# Controller.net
KiCad netlist of a schematic drawn in Altium Designer
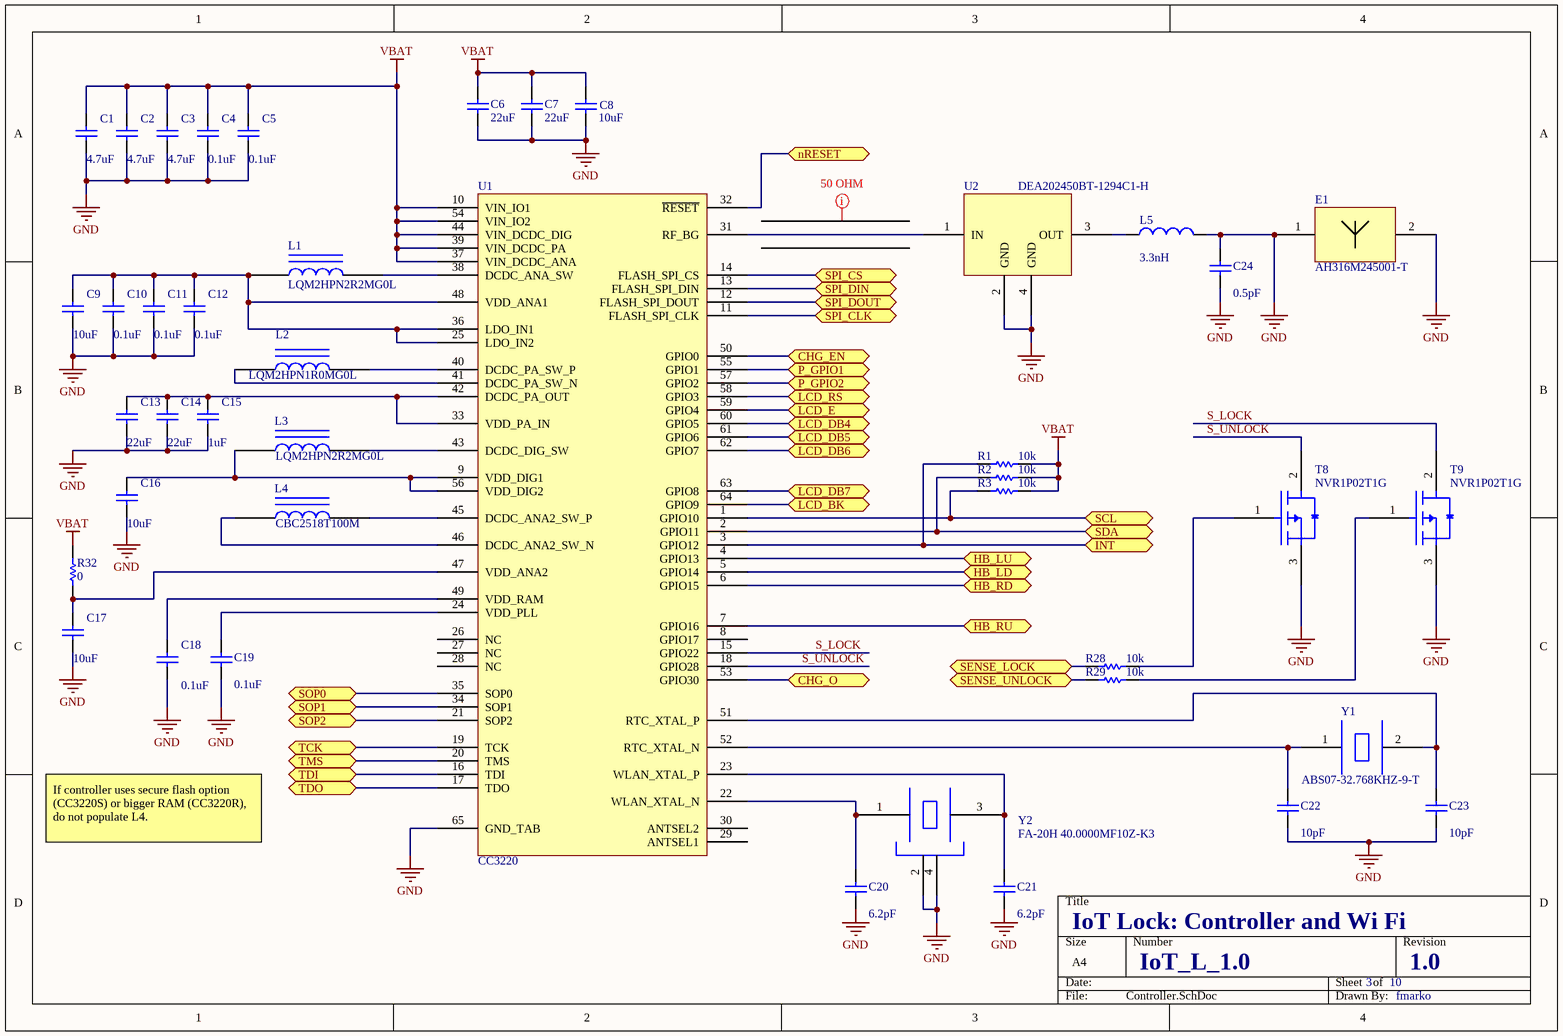
[diagram p0: Controller.SchDoc]

(export (version "E")
  (design (tool "Eeschema 10.0.6"))
  (components
    (comp (ref "C1")
      (value "4.7uF")
      (footprint "0402")
      (description "Capacitor")
      (fields (field (name "Comment") "GRM1555C1HR50BA01D") (field (name "PUBLISHER") "Altium Limited"))
      (libsource (lib "Miscellaneous Devices") (part "Cap"))
    )
    (comp (ref "C2")
      (value "4.7uF")
      (footprint "0402")
      (description "Capacitor")
      (fields (field (name "Comment") "GRM1555C1HR50BA01D") (field (name "PUBLISHER") "Altium Limited"))
      (libsource (lib "Miscellaneous Devices") (part "Cap"))
    )
    (comp (ref "C3")
      (value "4.7uF")
      (footprint "0402")
      (description "Capacitor")
      (fields (field (name "Comment") "GRM1555C1HR50BA01D") (field (name "PUBLISHER") "Altium Limited"))
      (libsource (lib "Miscellaneous Devices") (part "Cap"))
    )
    (comp (ref "C4")
      (value "0.1uF")
      (footprint "0402")
      (description "Capacitor")
      (fields (field (name "Comment") "GRM1555C1HR50BA01D") (field (name "PUBLISHER") "Altium Limited"))
      (libsource (lib "Miscellaneous Devices") (part "Cap"))
    )
    (comp (ref "C5")
      (value "0.1uF")
      (footprint "0402")
      (description "Capacitor")
      (fields (field (name "Comment") "GRM1555C1HR50BA01D") (field (name "PUBLISHER") "Altium Limited"))
      (libsource (lib "Miscellaneous Devices") (part "Cap"))
    )
    (comp (ref "C6")
      (value "22uF")
      (footprint "1608[0603]")
      (description "Capacitor")
      (fields (field (name "Comment") "GRM1555C1HR50BA01D") (field (name "PUBLISHER") "Altium Limited"))
      (libsource (lib "Miscellaneous Devices") (part "Cap"))
    )
    (comp (ref "C7")
      (value "22uF")
      (footprint "1608[0603]")
      (description "Capacitor")
      (fields (field (name "Comment") "GRM1555C1HR50BA01D") (field (name "PUBLISHER") "Altium Limited"))
      (libsource (lib "Miscellaneous Devices") (part "Cap"))
    )
    (comp (ref "C8")
      (value "10uF")
      (footprint "1608[0603]")
      (description "Capacitor")
      (fields (field (name "Comment") "GRM1555C1HR50BA01D") (field (name "PUBLISHER") "Altium Limited"))
      (libsource (lib "Miscellaneous Devices") (part "Cap"))
    )
    (comp (ref "C9")
      (value "10uF")
      (footprint "1608[0603]")
      (description "Capacitor")
      (fields (field (name "Comment") "GRM1555C1HR50BA01D") (field (name "PUBLISHER") "Altium Limited"))
      (libsource (lib "Miscellaneous Devices") (part "Cap"))
    )
    (comp (ref "C10")
      (value "0.1uF")
      (footprint "0402")
      (description "Capacitor")
      (fields (field (name "Comment") "GRM1555C1HR50BA01D") (field (name "PUBLISHER") "Altium Limited"))
      (libsource (lib "Miscellaneous Devices") (part "Cap"))
    )
    (comp (ref "C11")
      (value "0.1uF")
      (footprint "0402")
      (description "Capacitor")
      (fields (field (name "Comment") "GRM1555C1HR50BA01D") (field (name "PUBLISHER") "Altium Limited"))
      (libsource (lib "Miscellaneous Devices") (part "Cap"))
    )
    (comp (ref "C12")
      (value "0.1uF")
      (footprint "0402")
      (description "Capacitor")
      (fields (field (name "Comment") "GRM1555C1HR50BA01D") (field (name "PUBLISHER") "Altium Limited"))
      (libsource (lib "Miscellaneous Devices") (part "Cap"))
    )
    (comp (ref "C13")
      (value "22uF")
      (footprint "1608[0603]")
      (description "Capacitor")
      (fields (field (name "Comment") "GRM1555C1HR50BA01D") (field (name "PUBLISHER") "Altium Limited"))
      (libsource (lib "Miscellaneous Devices") (part "Cap"))
    )
    (comp (ref "C14")
      (value "22uF")
      (footprint "1608[0603]")
      (description "Capacitor")
      (fields (field (name "Comment") "GRM1555C1HR50BA01D") (field (name "PUBLISHER") "Altium Limited"))
      (libsource (lib "Miscellaneous Devices") (part "Cap"))
    )
    (comp (ref "C15")
      (value "1uF")
      (footprint "0402")
      (description "Capacitor")
      (fields (field (name "Comment") "GRM1555C1HR50BA01D") (field (name "PUBLISHER") "Altium Limited"))
      (libsource (lib "Miscellaneous Devices") (part "Cap"))
    )
    (comp (ref "C16")
      (value "10uF")
      (footprint "1608[0603]")
      (description "Capacitor")
      (fields (field (name "Comment") "GRM1555C1HR50BA01D") (field (name "PUBLISHER") "Altium Limited"))
      (libsource (lib "Miscellaneous Devices") (part "Cap"))
    )
    (comp (ref "C17")
      (value "10uF")
      (footprint "1608[0603]")
      (description "Capacitor")
      (fields (field (name "Comment") "GRM1555C1HR50BA01D") (field (name "PUBLISHER") "Altium Limited"))
      (libsource (lib "Miscellaneous Devices") (part "Cap"))
    )
    (comp (ref "C18")
      (value "0.1uF")
      (footprint "0402")
      (description "Capacitor")
      (fields (field (name "Comment") "GRM1555C1HR50BA01D") (field (name "PUBLISHER") "Altium Limited"))
      (libsource (lib "Miscellaneous Devices") (part "Cap"))
    )
    (comp (ref "C19")
      (value "0.1uF")
      (footprint "0402")
      (description "Capacitor")
      (fields (field (name "Comment") "GRM1555C1HR50BA01D") (field (name "PUBLISHER") "Altium Limited"))
      (libsource (lib "Miscellaneous Devices") (part "Cap"))
    )
    (comp (ref "C20")
      (value "6.2pF")
      (footprint "0402")
      (description "Capacitor")
      (fields (field (name "Comment") "GRM1555C1HR50BA01D") (field (name "PUBLISHER") "Altium Limited"))
      (libsource (lib "Miscellaneous Devices") (part "Cap"))
    )
    (comp (ref "C21")
      (value "6.2pF")
      (footprint "0402")
      (description "Capacitor")
      (fields (field (name "Comment") "GRM1555C1HR50BA01D") (field (name "PUBLISHER") "Altium Limited"))
      (libsource (lib "Miscellaneous Devices") (part "Cap"))
    )
    (comp (ref "C22")
      (value "10pF")
      (footprint "0402")
      (description "Capacitor")
      (fields (field (name "Comment") "GRM1555C1HR50BA01D") (field (name "PUBLISHER") "Altium Limited"))
      (libsource (lib "Miscellaneous Devices") (part "Cap"))
    )
    (comp (ref "C23")
      (value "10pF")
      (footprint "0402")
      (description "Capacitor")
      (fields (field (name "Comment") "GRM1555C1HR50BA01D") (field (name "PUBLISHER") "Altium Limited"))
      (libsource (lib "Miscellaneous Devices") (part "Cap"))
    )
    (comp (ref "C24")
      (value "0.5pF")
      (footprint "0402")
      (description "Capacitor")
      (fields (field (name "Comment") "GRM1555C1HR50BA01D") (field (name "PUBLISHER") "Altium Limited"))
      (libsource (lib "Miscellaneous Devices") (part "Cap"))
    )
    (comp (ref "E1")
      (value "AH316M245001-T")
      (footprint "AH316M245001-T")
      (description "2.4 GHz Antenna")
      (libsource (lib "AH316M245001-T") (part "AH316M245001-T"))
    )
    (comp (ref "L1")
      (value "LQM2HPN2R2MG0L")
      (footprint "INDC2520X10N")
      (description "Murata 2.2uH inductor")
      (libsource (lib "LQM2HPN2R2MG0L") (part "LQM2HPN2R2MG0L"))
    )
    (comp (ref "L2")
      (value "LQM2HPN1R0MG0L")
      (footprint "INDC2520X10N")
      (description "Murata 2.2uH inductor")
      (libsource (lib "LQM2HPN2R2MG0L") (part "LQM2HPN2R2MG0L"))
    )
    (comp (ref "L3")
      (value "LQM2HPN2R2MG0L")
      (footprint "INDC2520X10N")
      (description "Murata 2.2uH inductor")
      (libsource (lib "LQM2HPN2R2MG0L") (part "LQM2HPN2R2MG0L"))
    )
    (comp (ref "L4")
      (value "CBC2518T100M")
      (footprint "INDC2518X20N")
      (description "10 uH inductor, Taiyo Yuden")
      (libsource (lib "CBC2518T100M") (part "CBC2518T100M"))
    )
    (comp (ref "L5")
      (value "3.3nH")
      (footprint "0402-A")
      (description "Inductor")
      (fields (field (name "Comment") "LQG15HS3N3S02D") (field (name "PUBLISHER") "Altium Limited"))
      (libsource (lib "Miscellaneous Devices") (part "Inductor"))
    )
    (comp (ref "R1")
      (value "10k")
      (footprint "0402")
      (description "Semiconductor Resistor")
      (fields (field (name "Comment") "Res Semi") (field (name "PUBLISHER") "Altium Limited"))
      (libsource (lib "Miscellaneous Devices") (part "Res Semi"))
    )
    (comp (ref "R2")
      (value "10k")
      (footprint "0402")
      (description "Semiconductor Resistor")
      (fields (field (name "Comment") "Res Semi") (field (name "PUBLISHER") "Altium Limited"))
      (libsource (lib "Miscellaneous Devices") (part "Res Semi"))
    )
    (comp (ref "R3")
      (value "10k")
      (footprint "0402")
      (description "Semiconductor Resistor")
      (fields (field (name "Comment") "Res Semi") (field (name "PUBLISHER") "Altium Limited"))
      (libsource (lib "Miscellaneous Devices") (part "Res Semi"))
    )
    (comp (ref "R28")
      (value "10k")
      (footprint "0402")
      (description "Semiconductor Resistor")
      (fields (field (name "Comment") "Res Semi") (field (name "PUBLISHER") "Altium Limited"))
      (libsource (lib "Miscellaneous Devices") (part "Res Semi"))
    )
    (comp (ref "R29")
      (value "10k")
      (footprint "0402")
      (description "Semiconductor Resistor")
      (fields (field (name "Comment") "Res Semi") (field (name "PUBLISHER") "Altium Limited"))
      (libsource (lib "Miscellaneous Devices") (part "Res Semi"))
    )
    (comp (ref "R32")
      (value "0")
      (footprint "0402")
      (description "Semiconductor Resistor")
      (fields (field (name "Comment") "Res Semi") (field (name "PUBLISHER") "Altium Limited"))
      (libsource (lib "Miscellaneous Devices") (part "Res Semi"))
    )
    (comp (ref "T8")
      (value "NVR1P02T1G")
      (footprint "SOT95P237X111-3N")
      (description "P-Channel MOSFET")
      (libsource (lib "NVR1P02T1G") (part "NVR1P02T1G"))
    )
    (comp (ref "T9")
      (value "NVR1P02T1G")
      (footprint "SOT95P237X111-3N")
      (description "P-Channel MOSFET")
      (libsource (lib "NVR1P02T1G") (part "NVR1P02T1G"))
    )
    (comp (ref "U1")
      (value "CC3220")
      (footprint "PQFN50P900X900X100_HS-65N")
      (description "WiFi IoT controller, TI")
      (libsource (lib "CC3220") (part "CC3220"))
    )
    (comp (ref "U2")
      (value "DEA202450BT-1294C1-H")
      (footprint "DEA202450BT-1294C1-H_LAYOUT")
      (libsource (lib "DEA202450BT-1294C1-H") (part "DEA202450BT-1294C1-H"))
    )
    (comp (ref "Y1")
      (value "ABS07-32.768KHZ-9-T")
      (footprint "ABS07-32.768KHZ-9-T_HS")
      (description "32.768 kHz Crystal, Abracon LLC")
      (libsource (lib "ABS07-32.768KHZ-9-T") (part "ABS07-32.768KHZ-9-T"))
    )
    (comp (ref "Y2")
      (value "FA-20H 40.0000MF10Z-K3")
      (footprint "FA-20H 40.0000MF10Z-K3_HS")
      (description "Crystal, 40 MHz, 10pF, Epson")
      (libsource (lib "FA-20H 40.0000MF10Z-K3") (part "FA-20H 40.0000MF10Z-K3"))
    )
  )
  (nets
    (net (code "1") (name "/CHG_EN") (class "Default")
      (node (ref "U1") (pin "50") (pinfunction "GPIO0_50") (pintype "passive"))
    )
    (net (code "2") (name "/CHG_O") (class "Default")
      (node (ref "U1") (pin "53") (pinfunction "GPIO30_53") (pintype "passive"))
    )
    (net (code "3") (name "/HB_LD") (class "Default")
      (node (ref "U1") (pin "5") (pinfunction "GPIO14_5") (pintype "passive"))
    )
    (net (code "4") (name "/HB_LU") (class "Default")
      (node (ref "U1") (pin "4") (pinfunction "GPIO13_4") (pintype "passive"))
    )
    (net (code "5") (name "/HB_RD") (class "Default")
      (node (ref "U1") (pin "6") (pinfunction "GPIO15_6") (pintype "passive"))
    )
    (net (code "6") (name "/HB_RU") (class "Default")
      (node (ref "U1") (pin "7") (pinfunction "GPIO16_7") (pintype "passive"))
    )
    (net (code "7") (name "/INT") (class "Default")
      (node (ref "R1") (pin "1") (pinfunction "1_1") (pintype "passive"))
      (node (ref "U1") (pin "3") (pinfunction "GPIO12_3") (pintype "passive"))
    )
    (net (code "8") (name "/LCD_BK") (class "Default")
      (node (ref "U1") (pin "64") (pinfunction "GPIO9_64") (pintype "passive"))
    )
    (net (code "9") (name "/LCD_DB4") (class "Default")
      (node (ref "U1") (pin "60") (pinfunction "GPIO5_60") (pintype "passive"))
    )
    (net (code "10") (name "/LCD_DB5") (class "Default")
      (node (ref "U1") (pin "61") (pinfunction "GPIO6_61") (pintype "passive"))
    )
    (net (code "11") (name "/LCD_DB6") (class "Default")
      (node (ref "U1") (pin "62") (pinfunction "GPIO7_62") (pintype "passive"))
    )
    (net (code "12") (name "/LCD_DB7") (class "Default")
      (node (ref "U1") (pin "63") (pinfunction "GPIO8_63") (pintype "passive"))
    )
    (net (code "13") (name "/LCD_E") (class "Default")
      (node (ref "U1") (pin "59") (pinfunction "GPIO4_59") (pintype "passive"))
    )
    (net (code "14") (name "/LCD_RS") (class "Default")
      (node (ref "U1") (pin "58") (pinfunction "GPIO3_58") (pintype "passive"))
    )
    (net (code "15") (name "/P_GPIO1") (class "Default")
      (node (ref "U1") (pin "55") (pinfunction "GPIO1_55") (pintype "passive"))
    )
    (net (code "16") (name "/P_GPIO2") (class "Default")
      (node (ref "U1") (pin "57") (pinfunction "GPIO2_57") (pintype "passive"))
    )
    (net (code "17") (name "/SCL") (class "Default")
      (node (ref "R3") (pin "1") (pinfunction "1_1") (pintype "passive"))
      (node (ref "U1") (pin "1") (pinfunction "GPIO10_1") (pintype "passive"))
    )
    (net (code "18") (name "/SDA") (class "Default")
      (node (ref "R2") (pin "1") (pinfunction "1_1") (pintype "passive"))
      (node (ref "U1") (pin "2") (pinfunction "GPIO11_2") (pintype "passive"))
    )
    (net (code "19") (name "/SENSE_LOCK") (class "Default")
      (node (ref "R28") (pin "1") (pinfunction "1_1") (pintype "passive"))
    )
    (net (code "20") (name "/SENSE_UNLOCK") (class "Default")
      (node (ref "R29") (pin "1") (pinfunction "1_1") (pintype "passive"))
    )
    (net (code "21") (name "/SOP0") (class "Default")
      (node (ref "U1") (pin "35") (pinfunction "SOP0_35") (pintype "passive"))
    )
    (net (code "22") (name "/SOP1") (class "Default")
      (node (ref "U1") (pin "34") (pinfunction "SOP1_34") (pintype "passive"))
    )
    (net (code "23") (name "/SOP2") (class "Default")
      (node (ref "U1") (pin "21") (pinfunction "SOP2_21") (pintype "passive"))
    )
    (net (code "24") (name "/SPI_CLK") (class "Default")
      (node (ref "U1") (pin "11") (pinfunction "FLASH_SPI_CLK_11") (pintype "passive"))
    )
    (net (code "25") (name "/SPI_CS") (class "Default")
      (node (ref "U1") (pin "14") (pinfunction "FLASH_SPI_CS_14") (pintype "passive"))
    )
    (net (code "26") (name "/SPI_DIN") (class "Default")
      (node (ref "U1") (pin "13") (pinfunction "FLASH_SPI_DIN_13") (pintype "passive"))
    )
    (net (code "27") (name "/SPI_DOUT") (class "Default")
      (node (ref "U1") (pin "12") (pinfunction "FLASH_SPI_DOUT_12") (pintype "passive"))
    )
    (net (code "28") (name "/S_LOCK") (class "Default")
      (node (ref "T9") (pin "2") (pinfunction "S_2") (pintype "passive"))
      (node (ref "U1") (pin "15") (pinfunction "GPIO22_15") (pintype "passive"))
    )
    (net (code "29") (name "/S_UNLOCK") (class "Default")
      (node (ref "T8") (pin "2") (pinfunction "S_2") (pintype "passive"))
      (node (ref "U1") (pin "18") (pinfunction "GPIO28_18") (pintype "passive"))
    )
    (net (code "30") (name "/TCK") (class "Default")
      (node (ref "U1") (pin "19") (pinfunction "TCK_19") (pintype "passive"))
    )
    (net (code "31") (name "/TDI") (class "Default")
      (node (ref "U1") (pin "16") (pinfunction "TDI_16") (pintype "passive"))
    )
    (net (code "32") (name "/TDO") (class "Default")
      (node (ref "U1") (pin "17") (pinfunction "TDO_17") (pintype "passive"))
    )
    (net (code "33") (name "/TMS") (class "Default")
      (node (ref "U1") (pin "20") (pinfunction "TMS_20") (pintype "passive"))
    )
    (net (code "34") (name "/nRESET") (class "Default")
      (node (ref "U1") (pin "32") (pinfunction "~{RESET}_32") (pintype "passive"))
    )
    (net (code "35") (name "GND") (class "Default")
      (node (ref "C1") (pin "1") (pinfunction "1_1") (pintype "passive"))
      (node (ref "C10") (pin "1") (pinfunction "1_1") (pintype "passive"))
      (node (ref "C11") (pin "1") (pinfunction "1_1") (pintype "passive"))
      (node (ref "C12") (pin "1") (pinfunction "1_1") (pintype "passive"))
      (node (ref "C13") (pin "1") (pinfunction "1_1") (pintype "passive"))
      (node (ref "C14") (pin "1") (pinfunction "1_1") (pintype "passive"))
      (node (ref "C15") (pin "1") (pinfunction "1_1") (pintype "passive"))
      (node (ref "C16") (pin "1") (pinfunction "1_1") (pintype "passive"))
      (node (ref "C17") (pin "1") (pinfunction "1_1") (pintype "passive"))
      (node (ref "C18") (pin "1") (pinfunction "1_1") (pintype "passive"))
      (node (ref "C19") (pin "1") (pinfunction "1_1") (pintype "passive"))
      (node (ref "C2") (pin "1") (pinfunction "1_1") (pintype "passive"))
      (node (ref "C20") (pin "1") (pinfunction "1_1") (pintype "passive"))
      (node (ref "C21") (pin "1") (pinfunction "1_1") (pintype "passive"))
      (node (ref "C22") (pin "1") (pinfunction "1_1") (pintype "passive"))
      (node (ref "C23") (pin "1") (pinfunction "1_1") (pintype "passive"))
      (node (ref "C24") (pin "1") (pinfunction "1_1") (pintype "passive"))
      (node (ref "C24") (pin "2") (pinfunction "2_2") (pintype "passive"))
      (node (ref "C3") (pin "1") (pinfunction "1_1") (pintype "passive"))
      (node (ref "C4") (pin "1") (pinfunction "1_1") (pintype "passive"))
      (node (ref "C5") (pin "1") (pinfunction "1_1") (pintype "passive"))
      (node (ref "C6") (pin "1") (pinfunction "1_1") (pintype "passive"))
      (node (ref "C7") (pin "1") (pinfunction "1_1") (pintype "passive"))
      (node (ref "C8") (pin "1") (pinfunction "1_1") (pintype "passive"))
      (node (ref "C9") (pin "1") (pinfunction "1_1") (pintype "passive"))
      (node (ref "E1") (pin "1") (pintype "passive"))
      (node (ref "E1") (pin "2") (pintype "passive"))
      (node (ref "L5") (pin "2") (pinfunction "2_2") (pintype "passive"))
      (node (ref "T8") (pin "3") (pinfunction "D_3") (pintype "passive"))
      (node (ref "T9") (pin "3") (pinfunction "D_3") (pintype "passive"))
      (node (ref "U1") (pin "65") (pinfunction "GND_TAB_65") (pintype "passive"))
      (node (ref "U2") (pin "2") (pinfunction "GND_2") (pintype "passive"))
      (node (ref "U2") (pin "4") (pinfunction "GND_4") (pintype "passive"))
      (node (ref "Y2") (pin "2") (pintype "passive"))
      (node (ref "Y2") (pin "4") (pintype "passive"))
    )
    (net (code "36") (name "Net-(T8-G)") (class "Default")
      (node (ref "R28") (pin "2") (pinfunction "2_2") (pintype "passive"))
      (node (ref "T8") (pin "1") (pinfunction "G_1") (pintype "passive"))
    )
    (net (code "37") (name "Net-(T9-G)") (class "Default")
      (node (ref "R29") (pin "2") (pinfunction "2_2") (pintype "passive"))
      (node (ref "T9") (pin "1") (pinfunction "G_1") (pintype "passive"))
    )
    (net (code "38") (name "Net-(U1-DCDC_ANA2_SW_N)") (class "Default")
      (node (ref "L4") (pin "1") (pinfunction "1_1") (pintype "passive"))
      (node (ref "U1") (pin "46") (pinfunction "DCDC_ANA2_SW_N_46") (pintype "passive"))
    )
    (net (code "39") (name "Net-(U1-DCDC_ANA2_SW_P)") (class "Default")
      (node (ref "L4") (pin "2") (pinfunction "2_2") (pintype "passive"))
      (node (ref "U1") (pin "45") (pinfunction "DCDC_ANA2_SW_P_45") (pintype "passive"))
    )
    (net (code "40") (name "Net-(U1-DCDC_ANA_SW)") (class "Default")
      (node (ref "L1") (pin "2") (pinfunction "2_2") (pintype "passive"))
      (node (ref "U1") (pin "38") (pinfunction "DCDC_ANA_SW_38") (pintype "passive"))
    )
    (net (code "41") (name "Net-(U1-DCDC_DIG_SW)") (class "Default")
      (node (ref "L3") (pin "2") (pinfunction "2_2") (pintype "passive"))
      (node (ref "U1") (pin "43") (pinfunction "DCDC_DIG_SW_43") (pintype "passive"))
    )
    (net (code "42") (name "Net-(U1-DCDC_PA_OUT)") (class "Default")
      (node (ref "C13") (pin "2") (pinfunction "2_2") (pintype "passive"))
      (node (ref "C14") (pin "2") (pinfunction "2_2") (pintype "passive"))
      (node (ref "C15") (pin "2") (pinfunction "2_2") (pintype "passive"))
      (node (ref "U1") (pin "33") (pinfunction "VDD_PA_IN_33") (pintype "passive"))
      (node (ref "U1") (pin "42") (pinfunction "DCDC_PA_OUT_42") (pintype "passive"))
    )
    (net (code "43") (name "Net-(U1-DCDC_PA_SW_N)") (class "Default")
      (node (ref "L2") (pin "1") (pinfunction "1_1") (pintype "passive"))
      (node (ref "U1") (pin "41") (pinfunction "DCDC_PA_SW_N_41") (pintype "passive"))
    )
    (net (code "44") (name "Net-(U1-DCDC_PA_SW_P)") (class "Default")
      (node (ref "L2") (pin "2") (pinfunction "2_2") (pintype "passive"))
      (node (ref "U1") (pin "40") (pinfunction "DCDC_PA_SW_P_40") (pintype "passive"))
    )
    (net (code "45") (name "Net-(U1-LDO_IN1)") (class "Default")
      (node (ref "C10") (pin "2") (pinfunction "2_2") (pintype "passive"))
      (node (ref "C11") (pin "2") (pinfunction "2_2") (pintype "passive"))
      (node (ref "C12") (pin "2") (pinfunction "2_2") (pintype "passive"))
      (node (ref "C9") (pin "2") (pinfunction "2_2") (pintype "passive"))
      (node (ref "L1") (pin "1") (pinfunction "1_1") (pintype "passive"))
      (node (ref "U1") (pin "25") (pinfunction "LDO_IN2_25") (pintype "passive"))
      (node (ref "U1") (pin "36") (pinfunction "LDO_IN1_36") (pintype "passive"))
      (node (ref "U1") (pin "48") (pinfunction "VDD_ANA1_48") (pintype "passive"))
    )
    (net (code "46") (name "Net-(U1-RF_BG)") (class "Default")
      (node (ref "U1") (pin "31") (pinfunction "RF_BG_31") (pintype "passive"))
      (node (ref "U2") (pin "1") (pinfunction "IN_1") (pintype "passive"))
    )
    (net (code "47") (name "Net-(U1-RTC_XTAL_N)") (class "Default")
      (node (ref "C22") (pin "2") (pinfunction "2_2") (pintype "passive"))
      (node (ref "U1") (pin "52") (pinfunction "RTC_XTAL_N_52") (pintype "passive"))
      (node (ref "Y1") (pin "1") (pintype "passive"))
    )
    (net (code "48") (name "Net-(U1-RTC_XTAL_P)") (class "Default")
      (node (ref "C23") (pin "2") (pinfunction "2_2") (pintype "passive"))
      (node (ref "U1") (pin "51") (pinfunction "RTC_XTAL_P_51") (pintype "passive"))
      (node (ref "Y1") (pin "2") (pintype "passive"))
    )
    (net (code "49") (name "Net-(U1-VDD_ANA2)") (class "Default")
      (node (ref "C17") (pin "2") (pinfunction "2_2") (pintype "passive"))
      (node (ref "R32") (pin "1") (pinfunction "1_1") (pintype "passive"))
      (node (ref "U1") (pin "47") (pinfunction "VDD_ANA2_47") (pintype "passive"))
    )
    (net (code "50") (name "Net-(U1-VDD_DIG1)") (class "Default")
      (node (ref "C16") (pin "2") (pinfunction "2_2") (pintype "passive"))
      (node (ref "L3") (pin "1") (pinfunction "1_1") (pintype "passive"))
      (node (ref "U1") (pin "56") (pinfunction "VDD_DIG2_56") (pintype "passive"))
      (node (ref "U1") (pin "9") (pinfunction "VDD_DIG1_9") (pintype "passive"))
    )
    (net (code "51") (name "Net-(U1-VDD_PLL)") (class "Default")
      (node (ref "C19") (pin "2") (pinfunction "2_2") (pintype "passive"))
      (node (ref "U1") (pin "24") (pinfunction "VDD_PLL_24") (pintype "passive"))
    )
    (net (code "52") (name "Net-(U1-VDD_RAM)") (class "Default")
      (node (ref "C18") (pin "2") (pinfunction "2_2") (pintype "passive"))
      (node (ref "U1") (pin "49") (pinfunction "VDD_RAM_49") (pintype "passive"))
    )
    (net (code "53") (name "Net-(U1-WLAN_XTAL_N)") (class "Default")
      (node (ref "C20") (pin "2") (pinfunction "2_2") (pintype "passive"))
      (node (ref "U1") (pin "22") (pinfunction "WLAN_XTAL_N_22") (pintype "passive"))
      (node (ref "Y2") (pin "1") (pintype "passive"))
    )
    (net (code "54") (name "Net-(U1-WLAN_XTAL_P)") (class "Default")
      (node (ref "C21") (pin "2") (pinfunction "2_2") (pintype "passive"))
      (node (ref "U1") (pin "23") (pinfunction "WLAN_XTAL_P_23") (pintype "passive"))
      (node (ref "Y2") (pin "3") (pintype "passive"))
    )
    (net (code "55") (name "Net-(U2-OUT)") (class "Default")
      (node (ref "L5") (pin "1") (pinfunction "1_1") (pintype "passive"))
      (node (ref "U2") (pin "3") (pinfunction "OUT_3") (pintype "passive"))
    )
    (net (code "56") (name "VBAT") (class "Default")
      (node (ref "C1") (pin "2") (pinfunction "2_2") (pintype "passive"))
      (node (ref "C2") (pin "2") (pinfunction "2_2") (pintype "passive"))
      (node (ref "C3") (pin "2") (pinfunction "2_2") (pintype "passive"))
      (node (ref "C4") (pin "2") (pinfunction "2_2") (pintype "passive"))
      (node (ref "C5") (pin "2") (pinfunction "2_2") (pintype "passive"))
      (node (ref "C6") (pin "2") (pinfunction "2_2") (pintype "passive"))
      (node (ref "C7") (pin "2") (pinfunction "2_2") (pintype "passive"))
      (node (ref "C8") (pin "2") (pinfunction "2_2") (pintype "passive"))
      (node (ref "R1") (pin "2") (pinfunction "2_2") (pintype "passive"))
      (node (ref "R2") (pin "2") (pinfunction "2_2") (pintype "passive"))
      (node (ref "R3") (pin "2") (pinfunction "2_2") (pintype "passive"))
      (node (ref "R32") (pin "2") (pinfunction "2_2") (pintype "passive"))
      (node (ref "U1") (pin "10") (pinfunction "VIN_IO1_10") (pintype "passive"))
      (node (ref "U1") (pin "37") (pinfunction "VIN_DCDC_ANA_37") (pintype "passive"))
      (node (ref "U1") (pin "39") (pinfunction "VIN_DCDC_PA_39") (pintype "passive"))
      (node (ref "U1") (pin "44") (pinfunction "VIN_DCDC_DIG_44") (pintype "passive"))
      (node (ref "U1") (pin "54") (pinfunction "VIN_IO2_54") (pintype "passive"))
    )
    (net (code "57") (name "unconnected-(U1-ANTSEL1-Pad29)") (class "Default")
      (node (ref "U1") (pin "29") (pinfunction "ANTSEL1_29") (pintype "passive"))
    )
    (net (code "58") (name "unconnected-(U1-ANTSEL2-Pad30)") (class "Default")
      (node (ref "U1") (pin "30") (pinfunction "ANTSEL2_30") (pintype "passive"))
    )
    (net (code "59") (name "unconnected-(U1-GPIO17-Pad8)") (class "Default")
      (node (ref "U1") (pin "8") (pinfunction "GPIO17_8") (pintype "passive"))
    )
    (net (code "60") (name "unconnected-(U1-NC-Pad26)") (class "Default")
      (node (ref "U1") (pin "26") (pinfunction "NC_26") (pintype "passive"))
    )
    (net (code "61") (name "unconnected-(U1-NC-Pad27)") (class "Default")
      (node (ref "U1") (pin "27") (pinfunction "NC_27") (pintype "passive"))
    )
    (net (code "62") (name "unconnected-(U1-NC-Pad28)") (class "Default")
      (node (ref "U1") (pin "28") (pinfunction "NC_28") (pintype "passive"))
    )
  )
)
